# 310_usb_memory.net
KiCad netlist of a schematic drawn in EAGLE
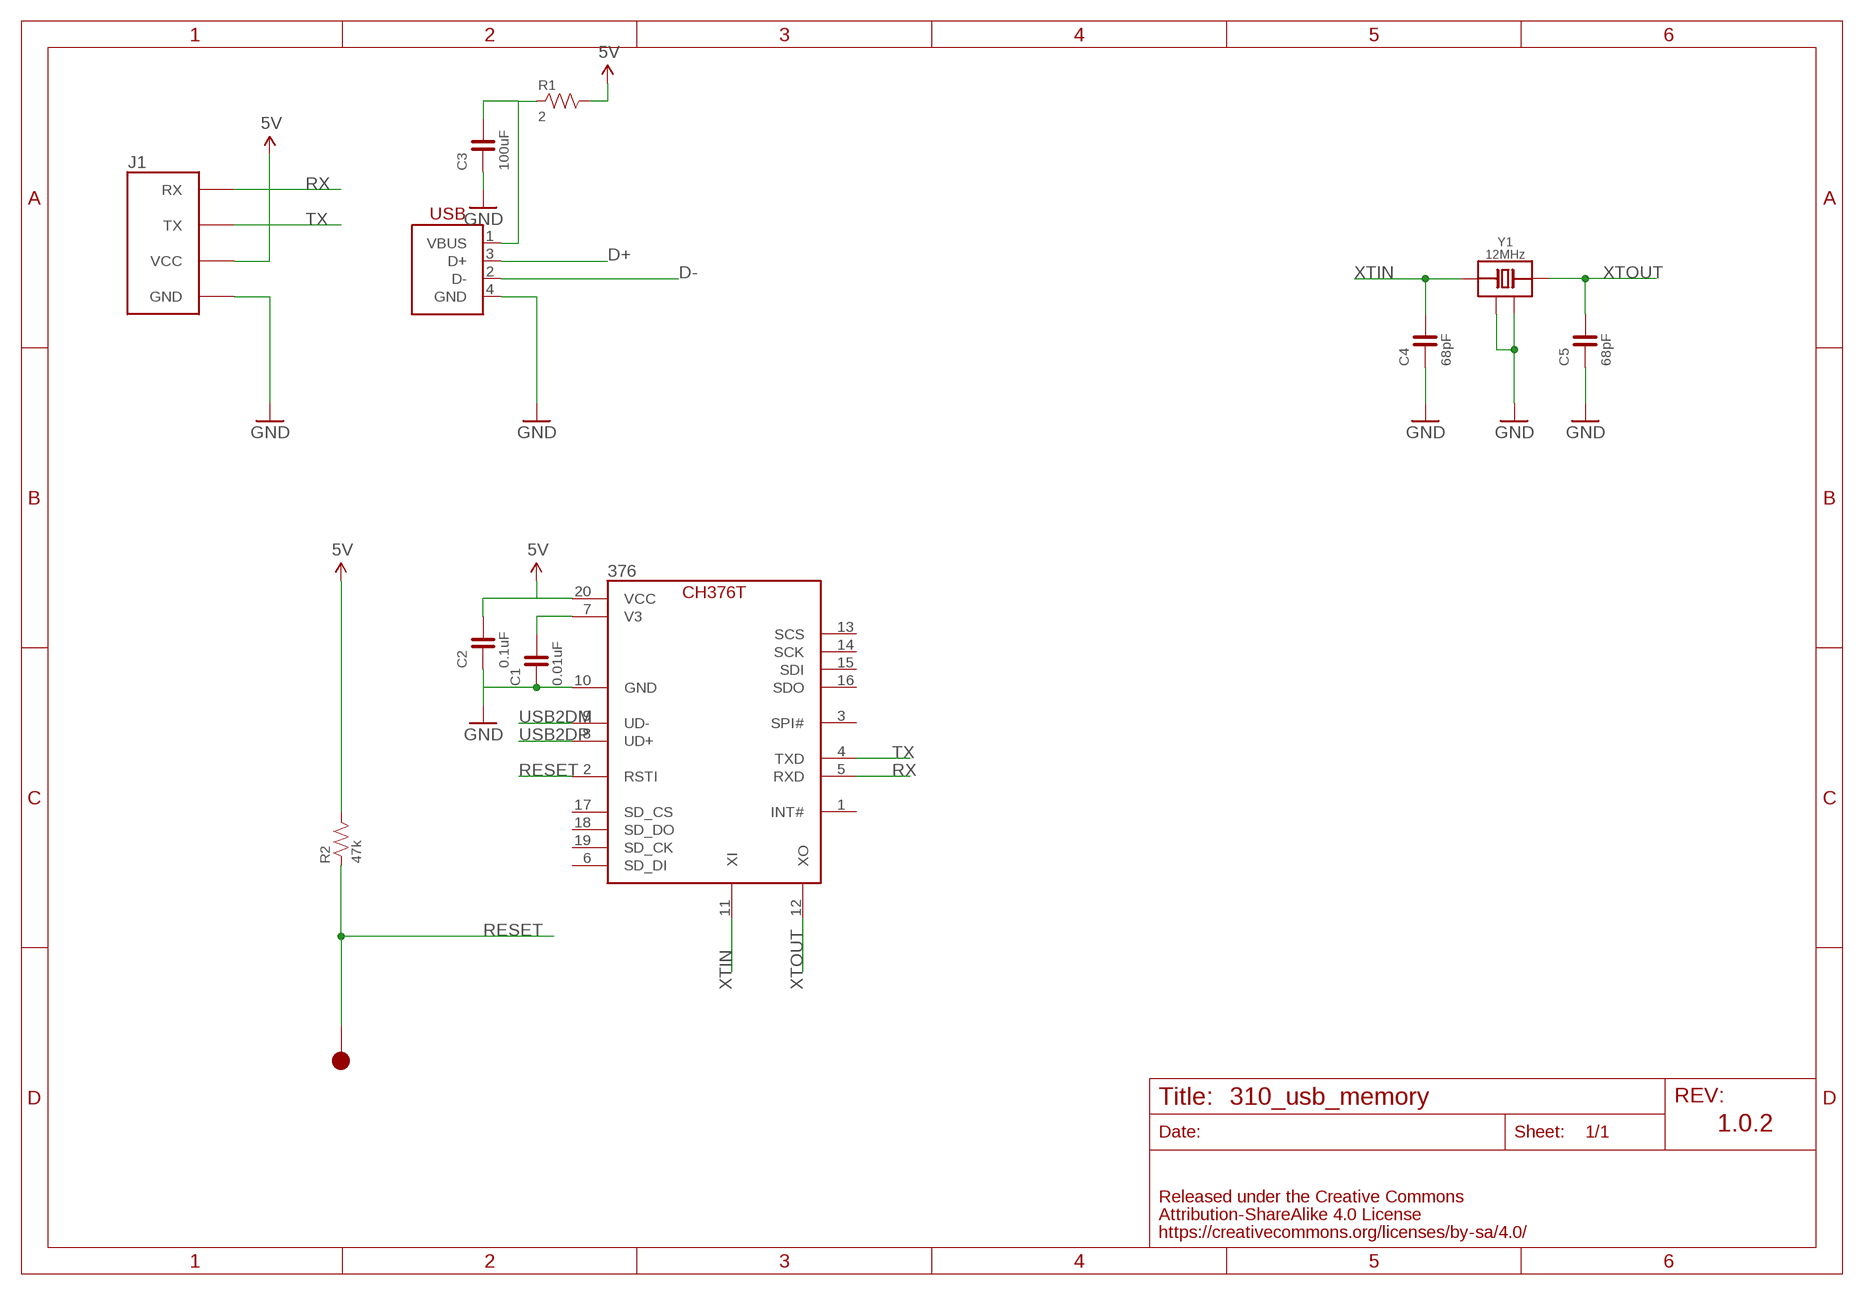
[diagram p0: schematic, sheet 1]

(export (version "E")
  (design (tool "Eeschema 10.0.6"))
  (components
    (comp (ref "376")
      (value "CH376T")
      (footprint "eagle-import:SSOP-20")
      (libsource (lib "eagle-import") (part "CH376T"))
    )
    (comp (ref "C1")
      (value "0.01uF")
      (footprint "eagle-import:0402")
      (libsource (lib "eagle-import") (part "CAPACITOR-0402"))
    )
    (comp (ref "C2")
      (value "0.1uF")
      (footprint "eagle-import:0402")
      (libsource (lib "eagle-import") (part "CAPACITOR-0402"))
    )
    (comp (ref "C3")
      (value "100uF")
      (footprint "eagle-import:0402")
      (libsource (lib "eagle-import") (part "CAPACITOR-0402"))
    )
    (comp (ref "C4")
      (value "68pF")
      (footprint "eagle-import:0402")
      (libsource (lib "eagle-import") (part "CAPACITOR-0402"))
    )
    (comp (ref "C5")
      (value "68pF")
      (footprint "eagle-import:0402")
      (libsource (lib "eagle-import") (part "CAPACITOR-0402"))
    )
    (comp (ref "J1")
      (value "FABO_BRICK_SERIAL")
      (footprint "eagle-import:FABO_BRICK_SERIAL")
      (libsource (lib "eagle-import") (part "FABO_BRICK_SERIAL"))
    )
    (comp (ref "R1")
      (value "2")
      (footprint "eagle-import:0402")
      (libsource (lib "eagle-import") (part "RESISTOR-0402"))
    )
    (comp (ref "R2")
      (value "47k")
      (footprint "eagle-import:0402")
      (libsource (lib "eagle-import") (part "RESISTOR-0402"))
    )
    (comp (ref "TP1")
      (value "TP-15")
      (footprint "eagle-import:TP-15")
      (libsource (lib "eagle-import") (part "TP-15"))
    )
    (comp (ref "USB1")
      (value "USB-B_PTH")
      (footprint "eagle-import:USB-4AF103BS")
      (libsource (lib "eagle-import") (part "USB-B_PTH"))
    )
    (comp (ref "Y1")
      (value "12MHz")
      (footprint "eagle-import:ECS-12MHZ")
      (libsource (lib "eagle-import") (part "CRYSTAL-ECS-120-12-33Q"))
    )
  )
  (nets
    (net (code "1") (name "/D+") (class "Default")
      (node (ref "USB1") (pin "3") (pinfunction "D+_3") (pintype "bidirectional"))
    )
    (net (code "2") (name "/D-") (class "Default")
      (node (ref "USB1") (pin "2") (pinfunction "D-_2") (pintype "bidirectional"))
    )
    (net (code "3") (name "/RESET") (class "Default")
      (node (ref "376") (pin "2") (pinfunction "RSTI_2") (pintype "bidirectional"))
      (node (ref "R2") (pin "P$1") (pinfunction "1_P$1") (pintype "bidirectional"))
      (node (ref "TP1") (pin "1") (pinfunction "1_1") (pintype "bidirectional"))
    )
    (net (code "4") (name "/RX") (class "Default")
      (node (ref "376") (pin "5") (pinfunction "RXD_5") (pintype "bidirectional"))
      (node (ref "J1") (pin "RX") (pinfunction "RX_RX") (pintype "bidirectional"))
    )
    (net (code "5") (name "/TX") (class "Default")
      (node (ref "376") (pin "4") (pinfunction "TXD_4") (pintype "bidirectional"))
      (node (ref "J1") (pin "TX") (pinfunction "TX_TX") (pintype "bidirectional"))
    )
    (net (code "6") (name "/USB2DM") (class "Default")
      (node (ref "376") (pin "9") (pinfunction "UD-_9") (pintype "bidirectional"))
    )
    (net (code "7") (name "/USB2DP") (class "Default")
      (node (ref "376") (pin "8") (pinfunction "UD+_8") (pintype "bidirectional"))
    )
    (net (code "8") (name "/XTIN") (class "Default")
      (node (ref "376") (pin "11") (pinfunction "XI_11") (pintype "bidirectional"))
      (node (ref "C4") (pin "P$2") (pinfunction "2_P$2") (pintype "passive"))
      (node (ref "Y1") (pin "1") (pinfunction "IO_1") (pintype "bidirectional"))
    )
    (net (code "9") (name "/XTOUT") (class "Default")
      (node (ref "376") (pin "12") (pinfunction "XO_12") (pintype "bidirectional"))
      (node (ref "C5") (pin "P$2") (pinfunction "2_P$2") (pintype "passive"))
      (node (ref "Y1") (pin "3") (pinfunction "IO_3") (pintype "bidirectional"))
    )
    (net (code "10") (name "5V") (class "Default")
      (node (ref "376") (pin "20") (pinfunction "VCC_20") (pintype "bidirectional"))
      (node (ref "C2") (pin "P$2") (pinfunction "2_P$2") (pintype "passive"))
      (node (ref "J1") (pin "VCC") (pinfunction "VCC_VCC") (pintype "bidirectional"))
      (node (ref "R1") (pin "P$2") (pinfunction "2_P$2") (pintype "bidirectional"))
      (node (ref "R2") (pin "P$2") (pinfunction "2_P$2") (pintype "bidirectional"))
    )
    (net (code "11") (name "GND") (class "Default")
      (node (ref "376") (pin "10") (pinfunction "GND_10") (pintype "bidirectional"))
      (node (ref "C1") (pin "P$1") (pinfunction "1_P$1") (pintype "passive"))
      (node (ref "C2") (pin "P$1") (pinfunction "1_P$1") (pintype "passive"))
      (node (ref "C3") (pin "P$1") (pinfunction "1_P$1") (pintype "passive"))
      (node (ref "C4") (pin "P$1") (pinfunction "1_P$1") (pintype "passive"))
      (node (ref "C5") (pin "P$1") (pinfunction "1_P$1") (pintype "passive"))
      (node (ref "J1") (pin "GND") (pinfunction "GND_GND") (pintype "bidirectional"))
      (node (ref "USB1") (pin "4") (pinfunction "GND_4") (pintype "bidirectional"))
      (node (ref "Y1") (pin "2") (pinfunction "GND_2") (pintype "bidirectional"))
      (node (ref "Y1") (pin "4") (pinfunction "GND_4") (pintype "bidirectional"))
    )
    (net (code "12") (name "Net-(376-V3)") (class "Default")
      (node (ref "376") (pin "7") (pinfunction "V3_7") (pintype "bidirectional"))
      (node (ref "C1") (pin "P$2") (pinfunction "2_P$2") (pintype "passive"))
    )
    (net (code "13") (name "Net-(C3-2)") (class "Default")
      (node (ref "C3") (pin "P$2") (pinfunction "2_P$2") (pintype "passive"))
      (node (ref "R1") (pin "P$1") (pinfunction "1_P$1") (pintype "bidirectional"))
      (node (ref "USB1") (pin "1") (pinfunction "VBUS_1") (pintype "bidirectional"))
    )
    (net (code "14") (name "unconnected-(376-INT#-Pad1)") (class "Default")
      (node (ref "376") (pin "1") (pinfunction "INT#_1") (pintype "bidirectional"))
    )
    (net (code "15") (name "unconnected-(376-SCK-Pad14)") (class "Default")
      (node (ref "376") (pin "14") (pinfunction "SCK_14") (pintype "bidirectional"))
    )
    (net (code "16") (name "unconnected-(376-SCS-Pad13)") (class "Default")
      (node (ref "376") (pin "13") (pinfunction "SCS_13") (pintype "bidirectional"))
    )
    (net (code "17") (name "unconnected-(376-SDI-Pad15)") (class "Default")
      (node (ref "376") (pin "15") (pinfunction "SDI_15") (pintype "bidirectional"))
    )
    (net (code "18") (name "unconnected-(376-SDO-Pad16)") (class "Default")
      (node (ref "376") (pin "16") (pinfunction "SDO_16") (pintype "bidirectional"))
    )
    (net (code "19") (name "unconnected-(376-SD_CK-Pad19)") (class "Default")
      (node (ref "376") (pin "19") (pinfunction "SD_CK_19") (pintype "bidirectional"))
    )
    (net (code "20") (name "unconnected-(376-SD_CS-Pad17)") (class "Default")
      (node (ref "376") (pin "17") (pinfunction "SD_CS_17") (pintype "bidirectional"))
    )
    (net (code "21") (name "unconnected-(376-SD_DI-Pad6)") (class "Default")
      (node (ref "376") (pin "6") (pinfunction "SD_DI_6") (pintype "bidirectional"))
    )
    (net (code "22") (name "unconnected-(376-SD_DO-Pad18)") (class "Default")
      (node (ref "376") (pin "18") (pinfunction "SD_DO_18") (pintype "bidirectional"))
    )
    (net (code "23") (name "unconnected-(376-SPI#-Pad3)") (class "Default")
      (node (ref "376") (pin "3") (pinfunction "SPI#_3") (pintype "bidirectional"))
    )
  )
)
